# rx-side.net
KiCad netlist of a schematic drawn in EAGLE
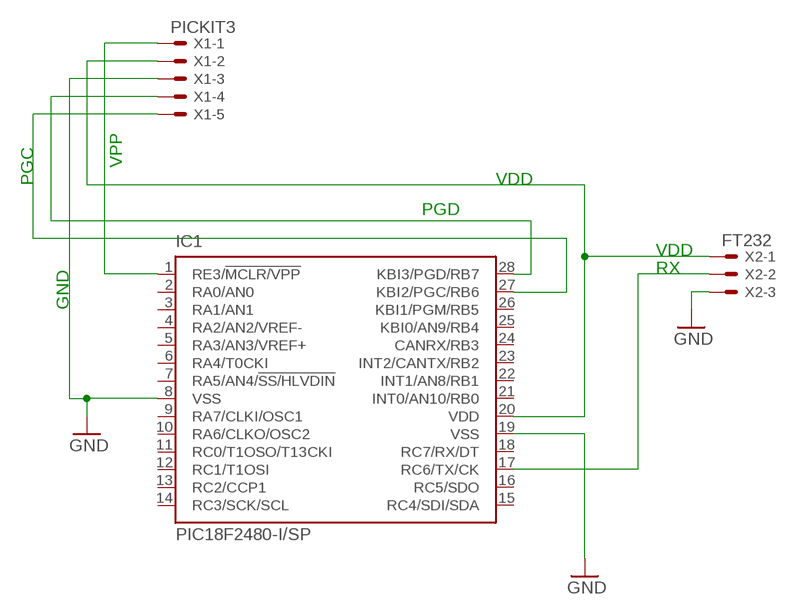
[diagram p0: schematic, sheet 1]

(export (version "E")
  (design (tool "Eeschema 10.0.6"))
  (components
    (comp (ref "IC1")
      (value "PIC18F2480-I/SP")
      (footprint "eagle-import:DIL28-3")
      (fields (field (name "MF") "MICROCHIP"))
      (libsource (lib "eagle-import") (part "PIC18F280-I/SP4"))
    )
    (comp (ref "X1")
      (value "PICKIT3")
      (footprint "eagle-import:22-23-2051")
      (fields (field (name "MF") "MOLEX") (field (name "MPN") "22-23-2051"))
      (libsource (lib "eagle-import") (part "22-23-2051"))
    )
    (comp (ref "X2")
      (value "FT232")
      (footprint "eagle-import:22-23-2031")
      (fields (field (name "MF") "MOLEX") (field (name "MPN") "22-23-2031"))
      (libsource (lib "eagle-import") (part "22-23-2031"))
    )
  )
  (nets
    (net (code "1") (name "GND") (class "Default")
      (node (ref "IC1") (pin "19") (pinfunction "VSS_19") (pintype "power_in"))
      (node (ref "IC1") (pin "8") (pinfunction "VSS_8") (pintype "power_in"))
      (node (ref "X1") (pin "3") (pinfunction "S_3") (pintype "passive"))
      (node (ref "X2") (pin "3") (pinfunction "S_3") (pintype "passive"))
    )
    (net (code "2") (name "Net-(IC1-KBI2{slash}PGC{slash}RB6)") (class "Default")
      (node (ref "IC1") (pin "27") (pinfunction "KBI2/PGC/RB6_27") (pintype "bidirectional"))
      (node (ref "X1") (pin "5") (pinfunction "S_5") (pintype "passive"))
    )
    (net (code "3") (name "Net-(IC1-KBI3{slash}PGD{slash}RB7)") (class "Default")
      (node (ref "IC1") (pin "28") (pinfunction "KBI3/PGD/RB7_28") (pintype "bidirectional"))
      (node (ref "X1") (pin "4") (pinfunction "S_4") (pintype "passive"))
    )
    (net (code "4") (name "Net-(IC1-RC6{slash}TX{slash}CK)") (class "Default")
      (node (ref "IC1") (pin "17") (pinfunction "RC6/TX/CK_17") (pintype "bidirectional"))
      (node (ref "X2") (pin "2") (pinfunction "S_2") (pintype "passive"))
    )
    (net (code "5") (name "Net-(IC1-RE3{slash}~{MCLR{slash}VPP})") (class "Default")
      (node (ref "IC1") (pin "1") (pinfunction "RE3/~{MCLR/VPP}_1") (pintype "input"))
      (node (ref "X1") (pin "1") (pinfunction "S_1") (pintype "passive"))
    )
    (net (code "6") (name "Net-(IC1-VDD)") (class "Default")
      (node (ref "IC1") (pin "20") (pinfunction "VDD_20") (pintype "power_in"))
      (node (ref "X1") (pin "2") (pinfunction "S_2") (pintype "passive"))
      (node (ref "X2") (pin "1") (pinfunction "S_1") (pintype "passive"))
    )
    (net (code "7") (name "unconnected-(IC1-CANRX{slash}RB3-Pad24)") (class "Default")
      (node (ref "IC1") (pin "24") (pinfunction "CANRX/RB3_24") (pintype "bidirectional"))
    )
    (net (code "8") (name "unconnected-(IC1-INT0{slash}AN10{slash}RB0-Pad21)") (class "Default")
      (node (ref "IC1") (pin "21") (pinfunction "INT0/AN10/RB0_21") (pintype "bidirectional"))
    )
    (net (code "9") (name "unconnected-(IC1-INT1{slash}AN8{slash}RB1-Pad22)") (class "Default")
      (node (ref "IC1") (pin "22") (pinfunction "INT1/AN8/RB1_22") (pintype "bidirectional"))
    )
    (net (code "10") (name "unconnected-(IC1-INT2{slash}CANTX{slash}RB2-Pad23)") (class "Default")
      (node (ref "IC1") (pin "23") (pinfunction "INT2/CANTX/RB2_23") (pintype "bidirectional"))
    )
    (net (code "11") (name "unconnected-(IC1-KBI0{slash}AN9{slash}RB4-Pad25)") (class "Default")
      (node (ref "IC1") (pin "25") (pinfunction "KBI0/AN9/RB4_25") (pintype "bidirectional"))
    )
    (net (code "12") (name "unconnected-(IC1-KBI1{slash}PGM{slash}RB5-Pad26)") (class "Default")
      (node (ref "IC1") (pin "26") (pinfunction "KBI1/PGM/RB5_26") (pintype "bidirectional"))
    )
    (net (code "13") (name "unconnected-(IC1-RA0{slash}AN0-Pad2)") (class "Default")
      (node (ref "IC1") (pin "2") (pinfunction "RA0/AN0_2") (pintype "bidirectional"))
    )
    (net (code "14") (name "unconnected-(IC1-RA1{slash}AN1-Pad3)") (class "Default")
      (node (ref "IC1") (pin "3") (pinfunction "RA1/AN1_3") (pintype "bidirectional"))
    )
    (net (code "15") (name "unconnected-(IC1-RA2{slash}AN2{slash}VREF--Pad4)") (class "Default")
      (node (ref "IC1") (pin "4") (pinfunction "RA2/AN2/VREF-_4") (pintype "bidirectional"))
    )
    (net (code "16") (name "unconnected-(IC1-RA3{slash}AN3{slash}VREF+-Pad5)") (class "Default")
      (node (ref "IC1") (pin "5") (pinfunction "RA3/AN3/VREF+_5") (pintype "bidirectional"))
    )
    (net (code "17") (name "unconnected-(IC1-RA4{slash}T0CKI-Pad6)") (class "Default")
      (node (ref "IC1") (pin "6") (pinfunction "RA4/T0CKI_6") (pintype "bidirectional"))
    )
    (net (code "18") (name "unconnected-(IC1-RA5{slash}AN4{slash}~{SS{slash}HLVDIN}-Pad7)") (class "Default")
      (node (ref "IC1") (pin "7") (pinfunction "RA5/AN4/~{SS/HLVDIN}_7") (pintype "bidirectional"))
    )
    (net (code "19") (name "unconnected-(IC1-RA6{slash}CLKO{slash}OSC2-Pad10)") (class "Default")
      (node (ref "IC1") (pin "10") (pinfunction "RA6/CLKO/OSC2_10") (pintype "output"))
    )
    (net (code "20") (name "unconnected-(IC1-RA7{slash}CLKI{slash}OSC1-Pad9)") (class "Default")
      (node (ref "IC1") (pin "9") (pinfunction "RA7/CLKI/OSC1_9") (pintype "input"))
    )
    (net (code "21") (name "unconnected-(IC1-RC0{slash}T1OSO{slash}T13CKI-Pad11)") (class "Default")
      (node (ref "IC1") (pin "11") (pinfunction "RC0/T1OSO/T13CKI_11") (pintype "bidirectional"))
    )
    (net (code "22") (name "unconnected-(IC1-RC1{slash}T1OSI-Pad12)") (class "Default")
      (node (ref "IC1") (pin "12") (pinfunction "RC1/T1OSI_12") (pintype "bidirectional"))
    )
    (net (code "23") (name "unconnected-(IC1-RC2{slash}CCP1-Pad13)") (class "Default")
      (node (ref "IC1") (pin "13") (pinfunction "RC2/CCP1_13") (pintype "bidirectional"))
    )
    (net (code "24") (name "unconnected-(IC1-RC3{slash}SCK{slash}SCL-Pad14)") (class "Default")
      (node (ref "IC1") (pin "14") (pinfunction "RC3/SCK/SCL_14") (pintype "bidirectional"))
    )
    (net (code "25") (name "unconnected-(IC1-RC4{slash}SDI{slash}SDA-Pad15)") (class "Default")
      (node (ref "IC1") (pin "15") (pinfunction "RC4/SDI/SDA_15") (pintype "bidirectional"))
    )
    (net (code "26") (name "unconnected-(IC1-RC5{slash}SDO-Pad16)") (class "Default")
      (node (ref "IC1") (pin "16") (pinfunction "RC5/SDO_16") (pintype "bidirectional"))
    )
    (net (code "27") (name "unconnected-(IC1-RC7{slash}RX{slash}DT-Pad18)") (class "Default")
      (node (ref "IC1") (pin "18") (pinfunction "RC7/RX/DT_18") (pintype "bidirectional"))
    )
  )
)
